# IR.net
KiCad netlist of a schematic drawn in EAGLE
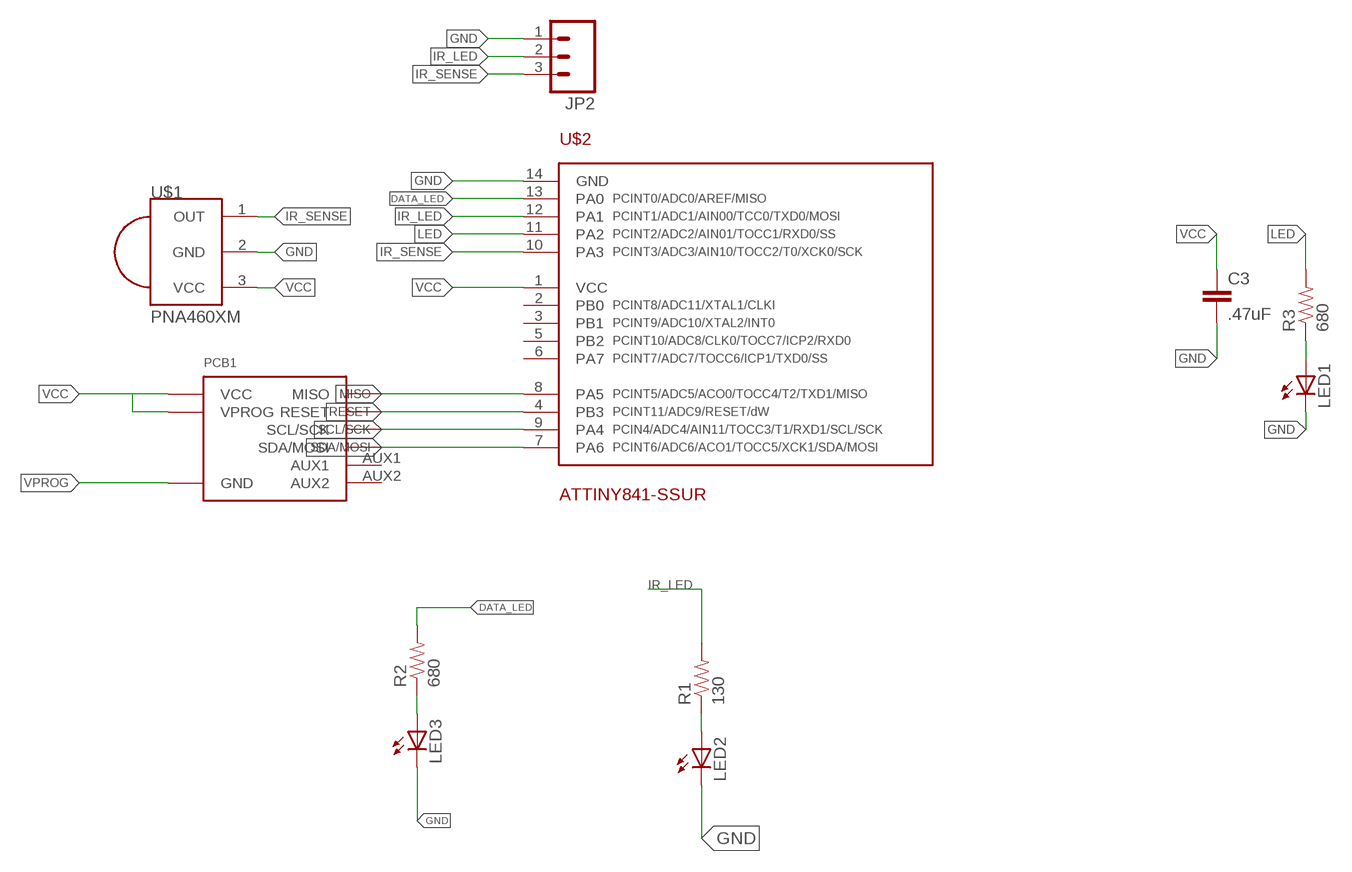
[diagram p0: schematic, sheet 1]

(export (version "E")
  (design (tool "Eeschema 10.0.6"))
  (components
    (comp (ref "C3")
      (value ".47uF")
      (footprint "eagle-import:0805")
      (libsource (lib "eagle-import") (part "CAP0805"))
    )
    (comp (ref "JP2")
      (value "M03PTH")
      (footprint "eagle-import:1X03")
      (libsource (lib "eagle-import") (part "M03PTH"))
    )
    (comp (ref "LED1")
      (value "LEDCHIP-LED0805")
      (footprint "eagle-import:CHIP-LED0805")
      (libsource (lib "eagle-import") (part "LEDCHIP-LED0805"))
    )
    (comp (ref "LED2")
      (value "LED5MM")
      (footprint "eagle-import:LED5MM")
      (libsource (lib "eagle-import") (part "LED5MM"))
    )
    (comp (ref "LED3")
      (value "LEDCHIP-LED0805")
      (footprint "eagle-import:CHIP-LED0805")
      (libsource (lib "eagle-import") (part "LEDCHIP-LED0805"))
    )
    (comp (ref "PCB1")
      (value "MAGDEVICE-V2")
      (footprint "eagle-import:MAGDEVICE-V2")
      (libsource (lib "eagle-import") (part "MAGDEVICE-V2"))
    )
    (comp (ref "R1")
      (value "130")
      (footprint "eagle-import:0805")
      (libsource (lib "eagle-import") (part "RESISTOR0805"))
    )
    (comp (ref "R2")
      (value "680")
      (footprint "eagle-import:0805")
      (libsource (lib "eagle-import") (part "RESISTOR0805"))
    )
    (comp (ref "R3")
      (value "680")
      (footprint "eagle-import:0805")
      (libsource (lib "eagle-import") (part "RESISTOR0805"))
    )
    (comp (ref "U$1")
      (value "PNA460XM")
      (footprint "eagle-import:PNA460XM")
      (libsource (lib "eagle-import") (part "PNA460XM"))
    )
    (comp (ref "U$2")
      (value "ATTINY841-SSUR")
      (footprint "eagle-import:SOIC-14")
      (libsource (lib "eagle-import") (part "ATTINY841"))
    )
  )
  (nets
    (net (code "1") (name "DATA_LED") (class "Default")
      (node (ref "R2") (pin "2") (pinfunction "2_2") (pintype "passive"))
      (node (ref "U$2") (pin "13") (pinfunction "PA0_13") (pintype "bidirectional"))
    )
    (net (code "2") (name "GND") (class "Default")
      (node (ref "C3") (pin "2") (pinfunction "2_2") (pintype "passive"))
      (node (ref "JP2") (pin "1") (pinfunction "1_1") (pintype "passive"))
      (node (ref "LED1") (pin "C") (pinfunction "C_C") (pintype "passive"))
      (node (ref "LED2") (pin "K") (pinfunction "C_K") (pintype "passive"))
      (node (ref "LED3") (pin "C") (pinfunction "C_C") (pintype "passive"))
      (node (ref "U$1") (pin "2") (pinfunction "GND_2") (pintype "power_in"))
      (node (ref "U$2") (pin "14") (pinfunction "GND_14") (pintype "bidirectional"))
    )
    (net (code "3") (name "IR_LED") (class "Default")
      (node (ref "JP2") (pin "2") (pinfunction "2_2") (pintype "passive"))
      (node (ref "R1") (pin "2") (pinfunction "2_2") (pintype "passive"))
      (node (ref "U$2") (pin "12") (pinfunction "PA1_12") (pintype "bidirectional"))
    )
    (net (code "4") (name "IR_SENSE") (class "Default")
      (node (ref "JP2") (pin "3") (pinfunction "3_3") (pintype "passive"))
      (node (ref "U$1") (pin "1") (pinfunction "OUT_1") (pintype "output"))
      (node (ref "U$2") (pin "10") (pinfunction "PA3_10") (pintype "bidirectional"))
    )
    (net (code "5") (name "LED") (class "Default")
      (node (ref "R3") (pin "2") (pinfunction "2_2") (pintype "passive"))
      (node (ref "U$2") (pin "11") (pinfunction "PA2_11") (pintype "bidirectional"))
    )
    (net (code "6") (name "MISO") (class "Default")
      (node (ref "PCB1") (pin "MISO") (pinfunction "MISO_MISO") (pintype "bidirectional"))
      (node (ref "U$2") (pin "8") (pinfunction "PA5_8") (pintype "bidirectional"))
    )
    (net (code "7") (name "Net-(LED1-PadA)") (class "Default")
      (node (ref "LED1") (pin "A") (pinfunction "A_A") (pintype "passive"))
      (node (ref "R3") (pin "1") (pinfunction "1_1") (pintype "passive"))
    )
    (net (code "8") (name "Net-(LED2-PadA)") (class "Default")
      (node (ref "LED2") (pin "A") (pinfunction "A_A") (pintype "passive"))
      (node (ref "R1") (pin "1") (pinfunction "1_1") (pintype "passive"))
    )
    (net (code "9") (name "Net-(LED3-PadA)") (class "Default")
      (node (ref "LED3") (pin "A") (pinfunction "A_A") (pintype "passive"))
      (node (ref "R2") (pin "1") (pinfunction "1_1") (pintype "passive"))
    )
    (net (code "10") (name "RESET") (class "Default")
      (node (ref "PCB1") (pin "RESET") (pinfunction "RESET_RESET") (pintype "bidirectional"))
      (node (ref "U$2") (pin "4") (pinfunction "PB3_4") (pintype "bidirectional"))
    )
    (net (code "11") (name "SCL{slash}SCK") (class "Default")
      (node (ref "PCB1") (pin "SCL") (pinfunction "SCL/SCK_SCL") (pintype "bidirectional"))
      (node (ref "U$2") (pin "9") (pinfunction "PA4_9") (pintype "bidirectional"))
    )
    (net (code "12") (name "SDA{slash}MOSI") (class "Default")
      (node (ref "PCB1") (pin "SDA") (pinfunction "SDA/MOSI_SDA") (pintype "bidirectional"))
      (node (ref "U$2") (pin "7") (pinfunction "PA6_7") (pintype "bidirectional"))
    )
    (net (code "13") (name "VCC") (class "Default")
      (node (ref "C3") (pin "1") (pinfunction "1_1") (pintype "passive"))
      (node (ref "PCB1") (pin "VCC") (pinfunction "VCC_VCC") (pintype "bidirectional"))
      (node (ref "PCB1") (pin "VPROG") (pinfunction "VPROG_VPROG") (pintype "bidirectional"))
      (node (ref "U$1") (pin "3") (pinfunction "VCC_3") (pintype "power_in"))
      (node (ref "U$2") (pin "1") (pinfunction "VCC_1") (pintype "bidirectional"))
    )
    (net (code "14") (name "VPROG") (class "Default")
      (node (ref "PCB1") (pin "GND") (pinfunction "GND_GND") (pintype "bidirectional"))
    )
    (net (code "15") (name "unconnected-(PCB1-PadAUX1)") (class "Default")
      (node (ref "PCB1") (pin "AUX1") (pinfunction "AUX1_AUX1") (pintype "bidirectional"))
    )
    (net (code "16") (name "unconnected-(PCB1-PadAUX2)") (class "Default")
      (node (ref "PCB1") (pin "AUX2") (pinfunction "AUX2_AUX2") (pintype "bidirectional"))
    )
    (net (code "17") (name "unconnected-(U$2-PA7-Pad6)") (class "Default")
      (node (ref "U$2") (pin "6") (pinfunction "PA7_6") (pintype "bidirectional"))
    )
    (net (code "18") (name "unconnected-(U$2-PB0-Pad2)") (class "Default")
      (node (ref "U$2") (pin "2") (pinfunction "PB0_2") (pintype "bidirectional"))
    )
    (net (code "19") (name "unconnected-(U$2-PB1-Pad3)") (class "Default")
      (node (ref "U$2") (pin "3") (pinfunction "PB1_3") (pintype "bidirectional"))
    )
    (net (code "20") (name "unconnected-(U$2-PB2-Pad5)") (class "Default")
      (node (ref "U$2") (pin "5") (pinfunction "PB2_5") (pintype "bidirectional"))
    )
  )
)
